# BT_module.net
KiCad netlist of a schematic drawn in EAGLE
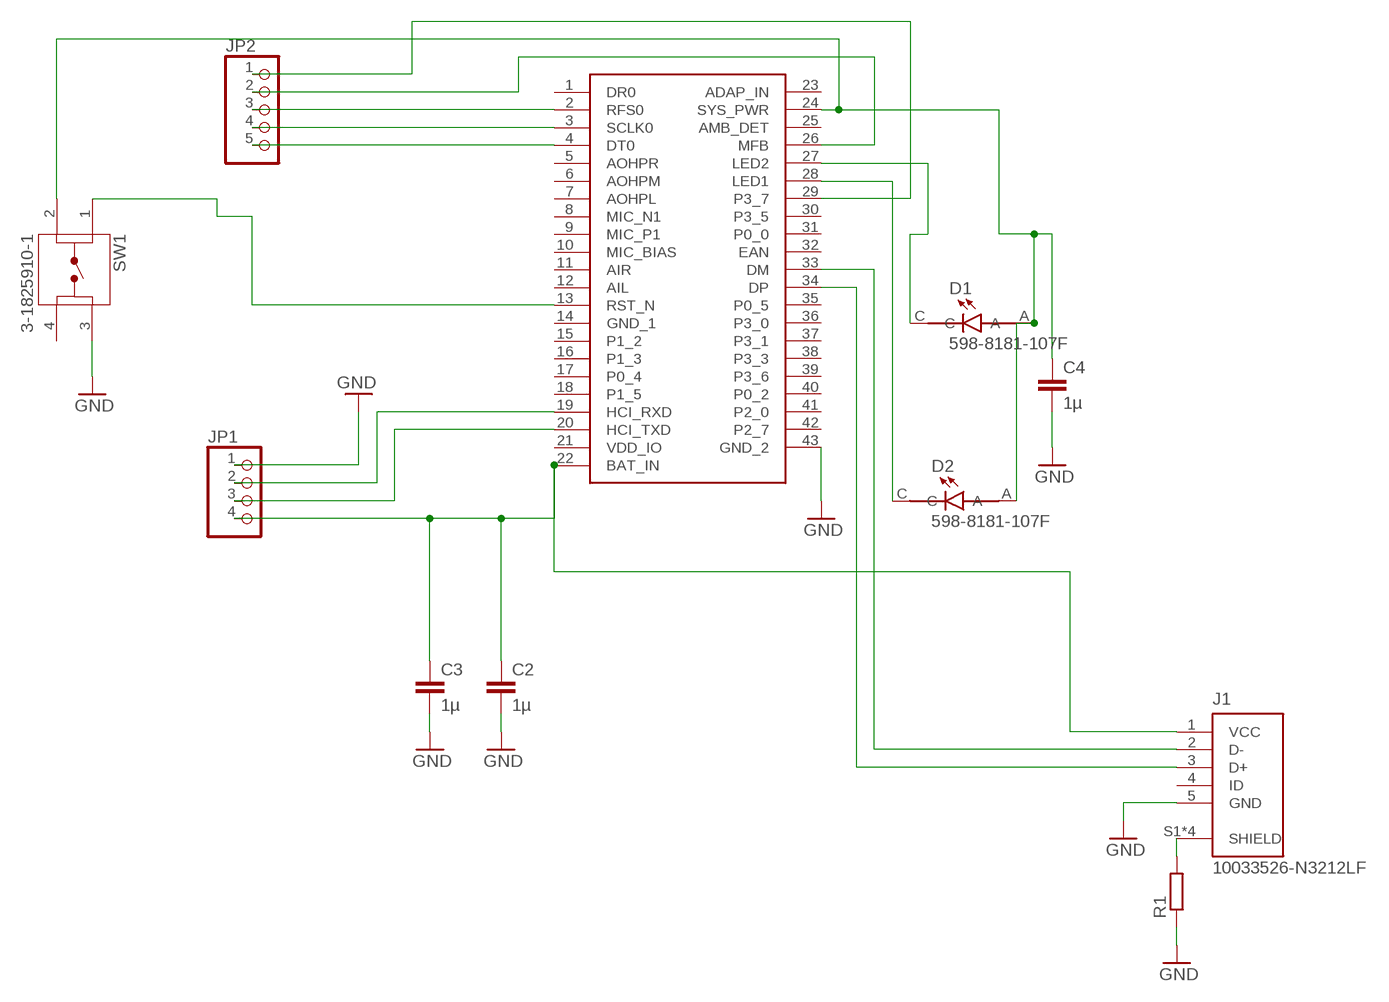
[diagram p0: schematic, sheet 1]

(export (version "E")
  (design (tool "Eeschema 10.0.6"))
  (components
    (comp (ref "ANT2")
      (value "BM64SPKS1MC2-0001AA")
      (footprint "eagle-import:BM64SPKS1MC20001AA")
      (fields (field (name "MF") "Microchip"))
      (libsource (lib "eagle-import") (part "BM64SPKS1MC2-0001AA"))
    )
    (comp (ref "C2")
      (value "1µ")
      (footprint "eagle-import:C0805")
      (libsource (lib "eagle-import") (part "C-EUC0805"))
    )
    (comp (ref "C3")
      (value "1µ")
      (footprint "eagle-import:C0805")
      (libsource (lib "eagle-import") (part "C-EUC0805"))
    )
    (comp (ref "C4")
      (value "1µ")
      (footprint "eagle-import:C0805")
      (libsource (lib "eagle-import") (part "C-EUC0805"))
    )
    (comp (ref "D1")
      (value "598-8181-107F")
      (footprint "eagle-import:LEDC2012X70N")
      (fields (field (name "MF") "Dialight"))
      (libsource (lib "eagle-import") (part "598-8181-107F"))
    )
    (comp (ref "D2")
      (value "598-8181-107F")
      (footprint "eagle-import:LEDC2012X70N")
      (fields (field (name "MF") "Dialight"))
      (libsource (lib "eagle-import") (part "598-8181-107F"))
    )
    (comp (ref "J1")
      (value "10033526-N3212LF")
      (footprint "eagle-import:AMPHENOL_10033526-N3212LF")
      (fields (field (name "MF") "Amphenol ICC (FCI)"))
      (libsource (lib "eagle-import") (part "10033526-N3212LF"))
    )
    (comp (ref "JP1")
      (value "PINHD-1X4")
      (footprint "eagle-import:1X04")
      (libsource (lib "eagle-import") (part "PINHD-1X4"))
    )
    (comp (ref "JP2")
      (value "PINHD-1X5")
      (footprint "eagle-import:1X05")
      (libsource (lib "eagle-import") (part "PINHD-1X5"))
    )
    (comp (ref "R1")
      (value "R-EU_M0805")
      (footprint "eagle-import:M0805")
      (libsource (lib "eagle-import") (part "R-EU_M0805"))
    )
    (comp (ref "SW1")
      (value "3-1825910-1")
      (footprint "eagle-import:TE_3-1825910-1")
      (fields (field (name "MF") "TE Connectivity"))
      (libsource (lib "eagle-import") (part "3-1825910-1"))
    )
  )
  (nets
    (net (code "1") (name "GND") (class "Default")
      (node (ref "ANT2") (pin "43") (pinfunction "GND_2_43") (pintype "bidirectional"))
      (node (ref "C2") (pin "2") (pinfunction "2_2") (pintype "passive"))
      (node (ref "C3") (pin "2") (pinfunction "2_2") (pintype "passive"))
      (node (ref "C4") (pin "2") (pinfunction "2_2") (pintype "passive"))
      (node (ref "J1") (pin "5") (pinfunction "GND_5") (pintype "power_in"))
      (node (ref "JP1") (pin "1") (pinfunction "1_1") (pintype "passive"))
      (node (ref "R1") (pin "1") (pinfunction "1_1") (pintype "passive"))
      (node (ref "SW1") (pin "3") (pinfunction "3_3") (pintype "passive"))
    )
    (net (code "2") (name "Net-(ANT2-BAT_IN)") (class "Default")
      (node (ref "ANT2") (pin "22") (pinfunction "BAT_IN_22") (pintype "bidirectional"))
      (node (ref "C2") (pin "1") (pinfunction "1_1") (pintype "passive"))
      (node (ref "C3") (pin "1") (pinfunction "1_1") (pintype "passive"))
      (node (ref "J1") (pin "1") (pinfunction "VCC_1") (pintype "power_in"))
      (node (ref "JP1") (pin "4") (pinfunction "4_4") (pintype "passive"))
    )
    (net (code "3") (name "Net-(ANT2-DM)") (class "Default")
      (node (ref "ANT2") (pin "33") (pinfunction "DM_33") (pintype "bidirectional"))
      (node (ref "J1") (pin "2") (pinfunction "D-_2") (pintype "bidirectional"))
    )
    (net (code "4") (name "Net-(ANT2-DP)") (class "Default")
      (node (ref "ANT2") (pin "34") (pinfunction "DP_34") (pintype "bidirectional"))
      (node (ref "J1") (pin "3") (pinfunction "D+_3") (pintype "bidirectional"))
    )
    (net (code "5") (name "Net-(ANT2-DT0)") (class "Default")
      (node (ref "ANT2") (pin "4") (pinfunction "DT0_4") (pintype "bidirectional"))
      (node (ref "JP2") (pin "5") (pinfunction "5_5") (pintype "passive"))
    )
    (net (code "6") (name "Net-(ANT2-HCI_RXD)") (class "Default")
      (node (ref "ANT2") (pin "19") (pinfunction "HCI_RXD_19") (pintype "bidirectional"))
      (node (ref "JP1") (pin "2") (pinfunction "2_2") (pintype "passive"))
    )
    (net (code "7") (name "Net-(ANT2-HCI_TXD)") (class "Default")
      (node (ref "ANT2") (pin "20") (pinfunction "HCI_TXD_20") (pintype "bidirectional"))
      (node (ref "JP1") (pin "3") (pinfunction "3_3") (pintype "passive"))
    )
    (net (code "8") (name "Net-(ANT2-LED1)") (class "Default")
      (node (ref "ANT2") (pin "28") (pinfunction "LED1_28") (pintype "bidirectional"))
      (node (ref "D2") (pin "C") (pinfunction "C_C") (pintype "passive"))
    )
    (net (code "9") (name "Net-(ANT2-LED2)") (class "Default")
      (node (ref "ANT2") (pin "27") (pinfunction "LED2_27") (pintype "bidirectional"))
      (node (ref "D1") (pin "C") (pinfunction "C_C") (pintype "passive"))
    )
    (net (code "10") (name "Net-(ANT2-MFB)") (class "Default")
      (node (ref "ANT2") (pin "26") (pinfunction "MFB_26") (pintype "bidirectional"))
      (node (ref "JP2") (pin "2") (pinfunction "2_2") (pintype "passive"))
    )
    (net (code "11") (name "Net-(ANT2-P3_7)") (class "Default")
      (node (ref "ANT2") (pin "29") (pinfunction "P3_7_29") (pintype "bidirectional"))
      (node (ref "JP2") (pin "1") (pinfunction "1_1") (pintype "passive"))
    )
    (net (code "12") (name "Net-(ANT2-RFS0)") (class "Default")
      (node (ref "ANT2") (pin "2") (pinfunction "RFS0_2") (pintype "bidirectional"))
      (node (ref "JP2") (pin "3") (pinfunction "3_3") (pintype "passive"))
    )
    (net (code "13") (name "Net-(ANT2-RST_N)") (class "Default")
      (node (ref "ANT2") (pin "13") (pinfunction "RST_N_13") (pintype "bidirectional"))
      (node (ref "SW1") (pin "1") (pinfunction "1_1") (pintype "passive"))
    )
    (net (code "14") (name "Net-(ANT2-SCLK0)") (class "Default")
      (node (ref "ANT2") (pin "3") (pinfunction "SCLK0_3") (pintype "bidirectional"))
      (node (ref "JP2") (pin "4") (pinfunction "4_4") (pintype "passive"))
    )
    (net (code "15") (name "Net-(ANT2-SYS_PWR)") (class "Default")
      (node (ref "ANT2") (pin "24") (pinfunction "SYS_PWR_24") (pintype "bidirectional"))
      (node (ref "C4") (pin "1") (pinfunction "1_1") (pintype "passive"))
      (node (ref "D1") (pin "A") (pinfunction "A_A") (pintype "passive"))
      (node (ref "D2") (pin "A") (pinfunction "A_A") (pintype "passive"))
      (node (ref "SW1") (pin "2") (pinfunction "2_2") (pintype "passive"))
    )
    (net (code "16") (name "Net-(J1-SHIELD-PadS1)") (class "Default")
      (node (ref "J1") (pin "S1") (pinfunction "SHIELD_S1") (pintype "passive"))
      (node (ref "J1") (pin "S2") (pinfunction "SHIELD_S2") (pintype "passive"))
      (node (ref "J1") (pin "S3") (pinfunction "SHIELD_S3") (pintype "passive"))
      (node (ref "J1") (pin "S4") (pinfunction "SHIELD_S4") (pintype "passive"))
      (node (ref "R1") (pin "2") (pinfunction "2_2") (pintype "passive"))
    )
    (net (code "17") (name "unconnected-(ANT2-ADAP_IN-Pad23)") (class "Default")
      (node (ref "ANT2") (pin "23") (pinfunction "ADAP_IN_23") (pintype "bidirectional"))
    )
    (net (code "18") (name "unconnected-(ANT2-AIL-Pad12)") (class "Default")
      (node (ref "ANT2") (pin "12") (pinfunction "AIL_12") (pintype "bidirectional"))
    )
    (net (code "19") (name "unconnected-(ANT2-AIR-Pad11)") (class "Default")
      (node (ref "ANT2") (pin "11") (pinfunction "AIR_11") (pintype "bidirectional"))
    )
    (net (code "20") (name "unconnected-(ANT2-AMB_DET-Pad25)") (class "Default")
      (node (ref "ANT2") (pin "25") (pinfunction "AMB_DET_25") (pintype "bidirectional"))
    )
    (net (code "21") (name "unconnected-(ANT2-AOHPL-Pad7)") (class "Default")
      (node (ref "ANT2") (pin "7") (pinfunction "AOHPL_7") (pintype "bidirectional"))
    )
    (net (code "22") (name "unconnected-(ANT2-AOHPM-Pad6)") (class "Default")
      (node (ref "ANT2") (pin "6") (pinfunction "AOHPM_6") (pintype "bidirectional"))
    )
    (net (code "23") (name "unconnected-(ANT2-AOHPR-Pad5)") (class "Default")
      (node (ref "ANT2") (pin "5") (pinfunction "AOHPR_5") (pintype "bidirectional"))
    )
    (net (code "24") (name "unconnected-(ANT2-DR0-Pad1)") (class "Default")
      (node (ref "ANT2") (pin "1") (pinfunction "DR0_1") (pintype "bidirectional"))
    )
    (net (code "25") (name "unconnected-(ANT2-EAN-Pad32)") (class "Default")
      (node (ref "ANT2") (pin "32") (pinfunction "EAN_32") (pintype "bidirectional"))
    )
    (net (code "26") (name "unconnected-(ANT2-GND_1-Pad14)") (class "Default")
      (node (ref "ANT2") (pin "14") (pinfunction "GND_1_14") (pintype "bidirectional"))
    )
    (net (code "27") (name "unconnected-(ANT2-MIC_BIAS-Pad10)") (class "Default")
      (node (ref "ANT2") (pin "10") (pinfunction "MIC_BIAS_10") (pintype "bidirectional"))
    )
    (net (code "28") (name "unconnected-(ANT2-MIC_N1-Pad8)") (class "Default")
      (node (ref "ANT2") (pin "8") (pinfunction "MIC_N1_8") (pintype "bidirectional"))
    )
    (net (code "29") (name "unconnected-(ANT2-MIC_P1-Pad9)") (class "Default")
      (node (ref "ANT2") (pin "9") (pinfunction "MIC_P1_9") (pintype "bidirectional"))
    )
    (net (code "30") (name "unconnected-(ANT2-P0_0-Pad31)") (class "Default")
      (node (ref "ANT2") (pin "31") (pinfunction "P0_0_31") (pintype "bidirectional"))
    )
    (net (code "31") (name "unconnected-(ANT2-P0_2-Pad40)") (class "Default")
      (node (ref "ANT2") (pin "40") (pinfunction "P0_2_40") (pintype "bidirectional"))
    )
    (net (code "32") (name "unconnected-(ANT2-P0_4-Pad17)") (class "Default")
      (node (ref "ANT2") (pin "17") (pinfunction "P0_4_17") (pintype "bidirectional"))
    )
    (net (code "33") (name "unconnected-(ANT2-P0_5-Pad35)") (class "Default")
      (node (ref "ANT2") (pin "35") (pinfunction "P0_5_35") (pintype "bidirectional"))
    )
    (net (code "34") (name "unconnected-(ANT2-P1_2-Pad15)") (class "Default")
      (node (ref "ANT2") (pin "15") (pinfunction "P1_2_15") (pintype "bidirectional"))
    )
    (net (code "35") (name "unconnected-(ANT2-P1_3-Pad16)") (class "Default")
      (node (ref "ANT2") (pin "16") (pinfunction "P1_3_16") (pintype "bidirectional"))
    )
    (net (code "36") (name "unconnected-(ANT2-P1_5-Pad18)") (class "Default")
      (node (ref "ANT2") (pin "18") (pinfunction "P1_5_18") (pintype "bidirectional"))
    )
    (net (code "37") (name "unconnected-(ANT2-P2_0-Pad41)") (class "Default")
      (node (ref "ANT2") (pin "41") (pinfunction "P2_0_41") (pintype "bidirectional"))
    )
    (net (code "38") (name "unconnected-(ANT2-P2_7-Pad42)") (class "Default")
      (node (ref "ANT2") (pin "42") (pinfunction "P2_7_42") (pintype "bidirectional"))
    )
    (net (code "39") (name "unconnected-(ANT2-P3_0-Pad36)") (class "Default")
      (node (ref "ANT2") (pin "36") (pinfunction "P3_0_36") (pintype "bidirectional"))
    )
    (net (code "40") (name "unconnected-(ANT2-P3_1-Pad37)") (class "Default")
      (node (ref "ANT2") (pin "37") (pinfunction "P3_1_37") (pintype "bidirectional"))
    )
    (net (code "41") (name "unconnected-(ANT2-P3_3-Pad38)") (class "Default")
      (node (ref "ANT2") (pin "38") (pinfunction "P3_3_38") (pintype "bidirectional"))
    )
    (net (code "42") (name "unconnected-(ANT2-P3_5-Pad30)") (class "Default")
      (node (ref "ANT2") (pin "30") (pinfunction "P3_5_30") (pintype "bidirectional"))
    )
    (net (code "43") (name "unconnected-(ANT2-P3_6-Pad39)") (class "Default")
      (node (ref "ANT2") (pin "39") (pinfunction "P3_6_39") (pintype "bidirectional"))
    )
    (net (code "44") (name "unconnected-(ANT2-VDD_IO-Pad21)") (class "Default")
      (node (ref "ANT2") (pin "21") (pinfunction "VDD_IO_21") (pintype "bidirectional"))
    )
    (net (code "45") (name "unconnected-(J1-ID-Pad4)") (class "Default")
      (node (ref "J1") (pin "4") (pinfunction "ID_4") (pintype "bidirectional"))
    )
    (net (code "46") (name "unconnected-(SW1-Pad4)") (class "Default")
      (node (ref "SW1") (pin "4") (pinfunction "4_4") (pintype "passive"))
    )
  )
)
